# WS2811-22_2024-06-16.net
KiCad netlist of a schematic drawn in EasyEDA Pro
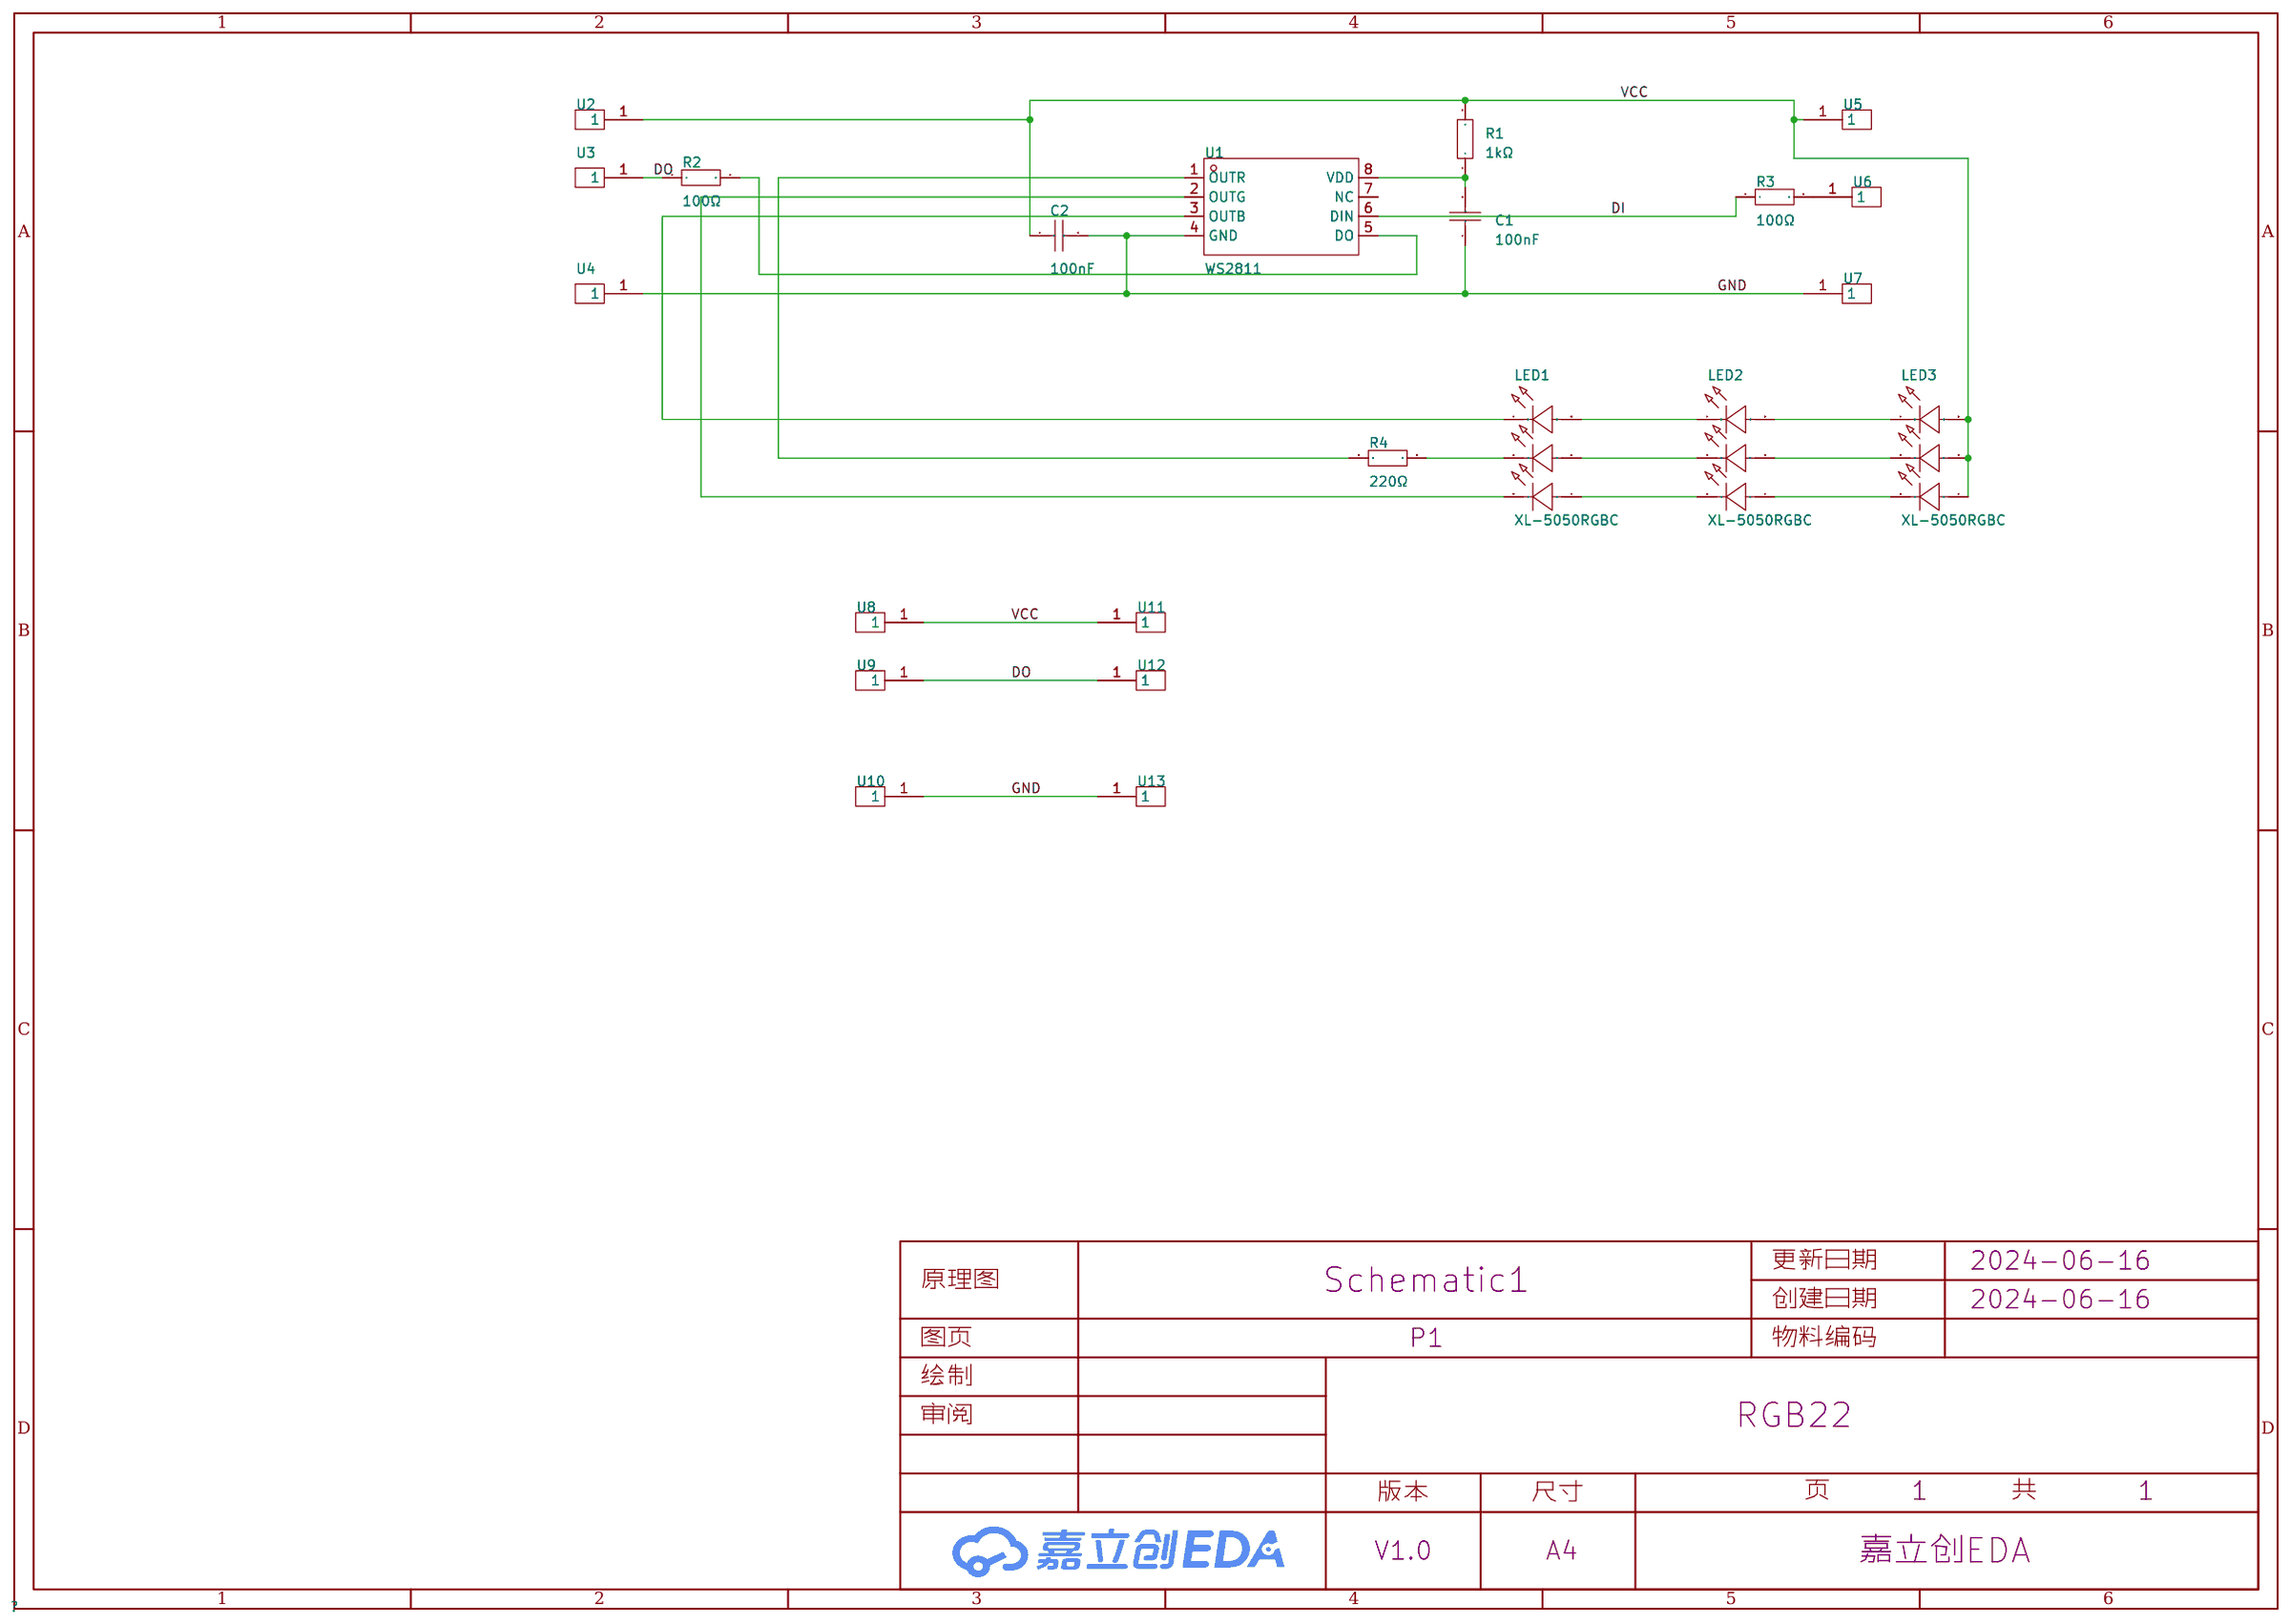
[diagram p0: schematic sheet]

(export (version "E")
  (design (tool "Eeschema 10.0.6"))
  (components
    (comp (ref "C1")
      (value "100nF")
      (footprint "easyedapro:C0805")
      (description "容值:100nF;精度:±10%;额定电压:50V;材质(温度系数):X7R;")
      (fields
        (field (name "Manufacturer Part") "CC0805KRX7R9BB104")
        (field (name "Manufacturer") "YAGEO(国巨)")
      )
      (libsource (lib "easyedapro") (part "CC0805KRX7R9BB104"))
    )
    (comp (ref "C2")
      (value "100nF")
      (footprint "easyedapro:C0805")
      (description "容值:100nF;精度:±10%;额定电压:50V;材质(温度系数):X7R;")
      (fields
        (field (name "Manufacturer Part") "CC0805KRX7R9BB104")
        (field (name "Manufacturer") "YAGEO(国巨)")
      )
      (libsource (lib "easyedapro") (part "CC0805KRX7R9BB104"))
    )
    (comp (ref "LED1")
      (value "XL-5050RGBC")
      (footprint "easyedapro:LED-ARRAY-SMD_6P-L5.0-W5.0-TL-RD_3")
      (fields (field (name "Manufacturer") "XINGLIGHT(成兴光)"))
      (libsource (lib "easyedapro") (part "XL-5050RGBC"))
    )
    (comp (ref "LED2")
      (value "XL-5050RGBC")
      (footprint "easyedapro:LED-ARRAY-SMD_6P-L5.0-W5.0-TL-RD_3")
      (fields (field (name "Manufacturer") "XINGLIGHT(成兴光)"))
      (libsource (lib "easyedapro") (part "XL-5050RGBC"))
    )
    (comp (ref "LED3")
      (value "XL-5050RGBC")
      (footprint "easyedapro:LED-ARRAY-SMD_6P-L5.0-W5.0-TL-RD_3")
      (fields (field (name "Manufacturer") "XINGLIGHT(成兴光)"))
      (libsource (lib "easyedapro") (part "XL-5050RGBC"))
    )
    (comp (ref "R1")
      (value "1kΩ")
      (footprint "easyedapro:R1206")
      (description "电阻类型:厚膜电阻;阻值:3kΩ;精度:±1%;功率:250mW;最大工作电压:200V;温度系数:±100ppm/°C;")
      (fields (field (name "Manufacturer Part") "RC0805FR-071KL") (field (name "Manufacturer") "YAGEO(国巨)"))
      (libsource (lib "easyedapro") (part "1206W4F3001T5E"))
    )
    (comp (ref "R2")
      (value "100Ω")
      (footprint "easyedapro:R1206")
      (description "电阻类型:厚膜电阻;阻值:100Ω;精度:±5%;功率:250mW;最大工作电压:200V;温度系数:±100ppm/°C;")
      (fields
        (field (name "Manufacturer Part") "0805W8F1000T5E")
        (field (name "Manufacturer") "UNI-ROYAL(厚声)")
      )
      (libsource (lib "easyedapro") (part "RC1206JR-07100RL"))
    )
    (comp (ref "R3")
      (value "100Ω")
      (footprint "easyedapro:R1206")
      (description "电阻类型:厚膜电阻;阻值:100Ω;精度:±5%;功率:250mW;最大工作电压:200V;温度系数:±100ppm/°C;")
      (fields
        (field (name "Manufacturer Part") "0805W8F1000T5E")
        (field (name "Manufacturer") "UNI-ROYAL(厚声)")
      )
      (libsource (lib "easyedapro") (part "RC1206JR-07100RL"))
    )
    (comp (ref "R4")
      (value "220Ω")
      (footprint "easyedapro:R1206")
      (description "电阻类型:厚膜电阻;阻值:390Ω;精度:±5%;功率:250mW;最大工作电压:200V;温度系数:±100ppm/°C;")
      (fields
        (field (name "Manufacturer Part") "0805W8F2200T5E")
        (field (name "Manufacturer") "UNI-ROYAL(厚声)")
      )
      (libsource (lib "easyedapro") (part "1206W4J0391T5E"))
    )
    (comp (ref "U1")
      (value "WS2811")
      (footprint "easyedapro:SOP-8_L4.9-W3.9-P1.27-LS6.0-BL")
      (description "类型:-;输入电压:-;开关频率:-;通道数:-;输出电压:-;输出电流:-;调光:-;拓扑结构:-;")
      (fields (field (name "Manufacturer") "worldsemi"))
      (libsource (lib "easyedapro") (part "WS2811"))
    )
    (comp (ref "U2")
      (value "~")
      (footprint "easyedapro:1.7X9")
      (libsource (lib "easyedapro") (part "1P1.7X9.5"))
    )
    (comp (ref "U3")
      (value "~")
      (footprint "easyedapro:1.7X9")
      (libsource (lib "easyedapro") (part "1P1.7X9.5"))
    )
    (comp (ref "U4")
      (value "~")
      (footprint "easyedapro:1.7X9")
      (libsource (lib "easyedapro") (part "1P1.7X9.5"))
    )
    (comp (ref "U5")
      (value "~")
      (footprint "easyedapro:1.7X9")
      (libsource (lib "easyedapro") (part "1P1.7X9.5"))
    )
    (comp (ref "U6")
      (value "~")
      (footprint "easyedapro:1.7X9")
      (libsource (lib "easyedapro") (part "1P1.7X9.5"))
    )
    (comp (ref "U7")
      (value "~")
      (footprint "easyedapro:1.7X9")
      (libsource (lib "easyedapro") (part "1P1.7X9.5"))
    )
    (comp (ref "U8")
      (value "~")
      (footprint "easyedapro:1.7X9")
      (libsource (lib "easyedapro") (part "1P1.7X9.5"))
    )
    (comp (ref "U9")
      (value "~")
      (footprint "easyedapro:1.7X9")
      (libsource (lib "easyedapro") (part "1P1.7X9.5"))
    )
    (comp (ref "U10")
      (value "~")
      (footprint "easyedapro:1.7X9")
      (libsource (lib "easyedapro") (part "1P1.7X9.5"))
    )
    (comp (ref "U11")
      (value "~")
      (footprint "easyedapro:1.7X9")
      (libsource (lib "easyedapro") (part "1P1.7X9.5"))
    )
    (comp (ref "U12")
      (value "~")
      (footprint "easyedapro:1.7X9")
      (libsource (lib "easyedapro") (part "1P1.7X9.5"))
    )
    (comp (ref "U13")
      (value "~")
      (footprint "easyedapro:1.7X9")
      (libsource (lib "easyedapro") (part "1P1.7X9.5"))
    )
  )
  (nets
    (net (code "1") (name "/DI") (class "Default")
      (node (ref "R3") (pin "1") (pinfunction "1_1") (pintype "input"))
      (node (ref "U1") (pin "6") (pinfunction "DIN_6") (pintype "unspecified"))
    )
    (net (code "2") (name "/DO") (class "Default")
      (node (ref "R2") (pin "1") (pinfunction "1_1") (pintype "input"))
      (node (ref "U12") (pin "1") (pinfunction "1_1") (pintype "input"))
      (node (ref "U3") (pin "1") (pinfunction "1_1") (pintype "input"))
      (node (ref "U9") (pin "1") (pinfunction "1_1") (pintype "input"))
    )
    (net (code "3") (name "/GND") (class "Default")
      (node (ref "C1") (pin "1") (pinfunction "1_1") (pintype "input"))
      (node (ref "C2") (pin "2") (pinfunction "2_2") (pintype "input"))
      (node (ref "U1") (pin "4") (pinfunction "GND_4") (pintype "unspecified"))
      (node (ref "U10") (pin "1") (pinfunction "1_1") (pintype "input"))
      (node (ref "U13") (pin "1") (pinfunction "1_1") (pintype "input"))
      (node (ref "U4") (pin "1") (pinfunction "1_1") (pintype "input"))
      (node (ref "U7") (pin "1") (pinfunction "1_1") (pintype "input"))
    )
    (net (code "4") (name "/VCC") (class "Default")
      (node (ref "C2") (pin "1") (pinfunction "1_1") (pintype "input"))
      (node (ref "LED3") (pin "4") (pinfunction "G+_4") (pintype "unspecified"))
      (node (ref "LED3") (pin "5") (pinfunction "R+_5") (pintype "unspecified"))
      (node (ref "LED3") (pin "6") (pinfunction "B+_6") (pintype "unspecified"))
      (node (ref "R1") (pin "2") (pinfunction "2_2") (pintype "input"))
      (node (ref "U11") (pin "1") (pinfunction "1_1") (pintype "input"))
      (node (ref "U2") (pin "1") (pinfunction "1_1") (pintype "input"))
      (node (ref "U5") (pin "1") (pinfunction "1_1") (pintype "input"))
      (node (ref "U8") (pin "1") (pinfunction "1_1") (pintype "input"))
    )
    (net (code "5") (name "Net-(LED1-B+)") (class "Default")
      (node (ref "LED1") (pin "6") (pinfunction "B+_6") (pintype "unspecified"))
      (node (ref "LED2") (pin "1") (pinfunction "B-_1") (pintype "unspecified"))
    )
    (net (code "6") (name "Net-(LED1-B-)") (class "Default")
      (node (ref "LED1") (pin "1") (pinfunction "B-_1") (pintype "unspecified"))
      (node (ref "U1") (pin "3") (pinfunction "OUTB_3") (pintype "unspecified"))
    )
    (net (code "7") (name "Net-(LED1-G+)") (class "Default")
      (node (ref "LED1") (pin "4") (pinfunction "G+_4") (pintype "unspecified"))
      (node (ref "LED2") (pin "3") (pinfunction "G-_3") (pintype "unspecified"))
    )
    (net (code "8") (name "Net-(LED1-G-)") (class "Default")
      (node (ref "LED1") (pin "3") (pinfunction "G-_3") (pintype "unspecified"))
      (node (ref "U1") (pin "2") (pinfunction "OUTG_2") (pintype "unspecified"))
    )
    (net (code "9") (name "Net-(LED1-R+)") (class "Default")
      (node (ref "LED1") (pin "5") (pinfunction "R+_5") (pintype "unspecified"))
      (node (ref "LED2") (pin "2") (pinfunction "R-_2") (pintype "unspecified"))
    )
    (net (code "10") (name "Net-(LED1-R-)") (class "Default")
      (node (ref "LED1") (pin "2") (pinfunction "R-_2") (pintype "unspecified"))
      (node (ref "R4") (pin "2") (pinfunction "2_2") (pintype "input"))
    )
    (net (code "11") (name "Net-(LED2-B+)") (class "Default")
      (node (ref "LED2") (pin "6") (pinfunction "B+_6") (pintype "unspecified"))
      (node (ref "LED3") (pin "1") (pinfunction "B-_1") (pintype "unspecified"))
    )
    (net (code "12") (name "Net-(LED2-G+)") (class "Default")
      (node (ref "LED2") (pin "4") (pinfunction "G+_4") (pintype "unspecified"))
      (node (ref "LED3") (pin "3") (pinfunction "G-_3") (pintype "unspecified"))
    )
    (net (code "13") (name "Net-(LED2-R+)") (class "Default")
      (node (ref "LED2") (pin "5") (pinfunction "R+_5") (pintype "unspecified"))
      (node (ref "LED3") (pin "2") (pinfunction "R-_2") (pintype "unspecified"))
    )
    (net (code "14") (name "Net-(R3-Pad2)") (class "Default")
      (node (ref "R3") (pin "2") (pinfunction "2_2") (pintype "input"))
      (node (ref "U6") (pin "1") (pinfunction "1_1") (pintype "input"))
    )
    (net (code "15") (name "Net-(U1-DO)") (class "Default")
      (node (ref "R2") (pin "2") (pinfunction "2_2") (pintype "input"))
      (node (ref "U1") (pin "5") (pinfunction "DO_5") (pintype "unspecified"))
    )
    (net (code "16") (name "Net-(U1-OUTR)") (class "Default")
      (node (ref "R4") (pin "1") (pinfunction "1_1") (pintype "input"))
      (node (ref "U1") (pin "1") (pinfunction "OUTR_1") (pintype "unspecified"))
    )
    (net (code "17") (name "Net-(U1-VDD)") (class "Default")
      (node (ref "C1") (pin "2") (pinfunction "2_2") (pintype "input"))
      (node (ref "R1") (pin "1") (pinfunction "1_1") (pintype "input"))
      (node (ref "U1") (pin "8") (pinfunction "VDD_8") (pintype "unspecified"))
    )
    (net (code "18") (name "unconnected-(U1-NC-Pad7)") (class "Default")
      (node (ref "U1") (pin "7") (pinfunction "NC_7") (pintype "unspecified"))
    )
  )
)
